# 05-STM32.net
KiCad netlist of a schematic drawn in Altium Designer
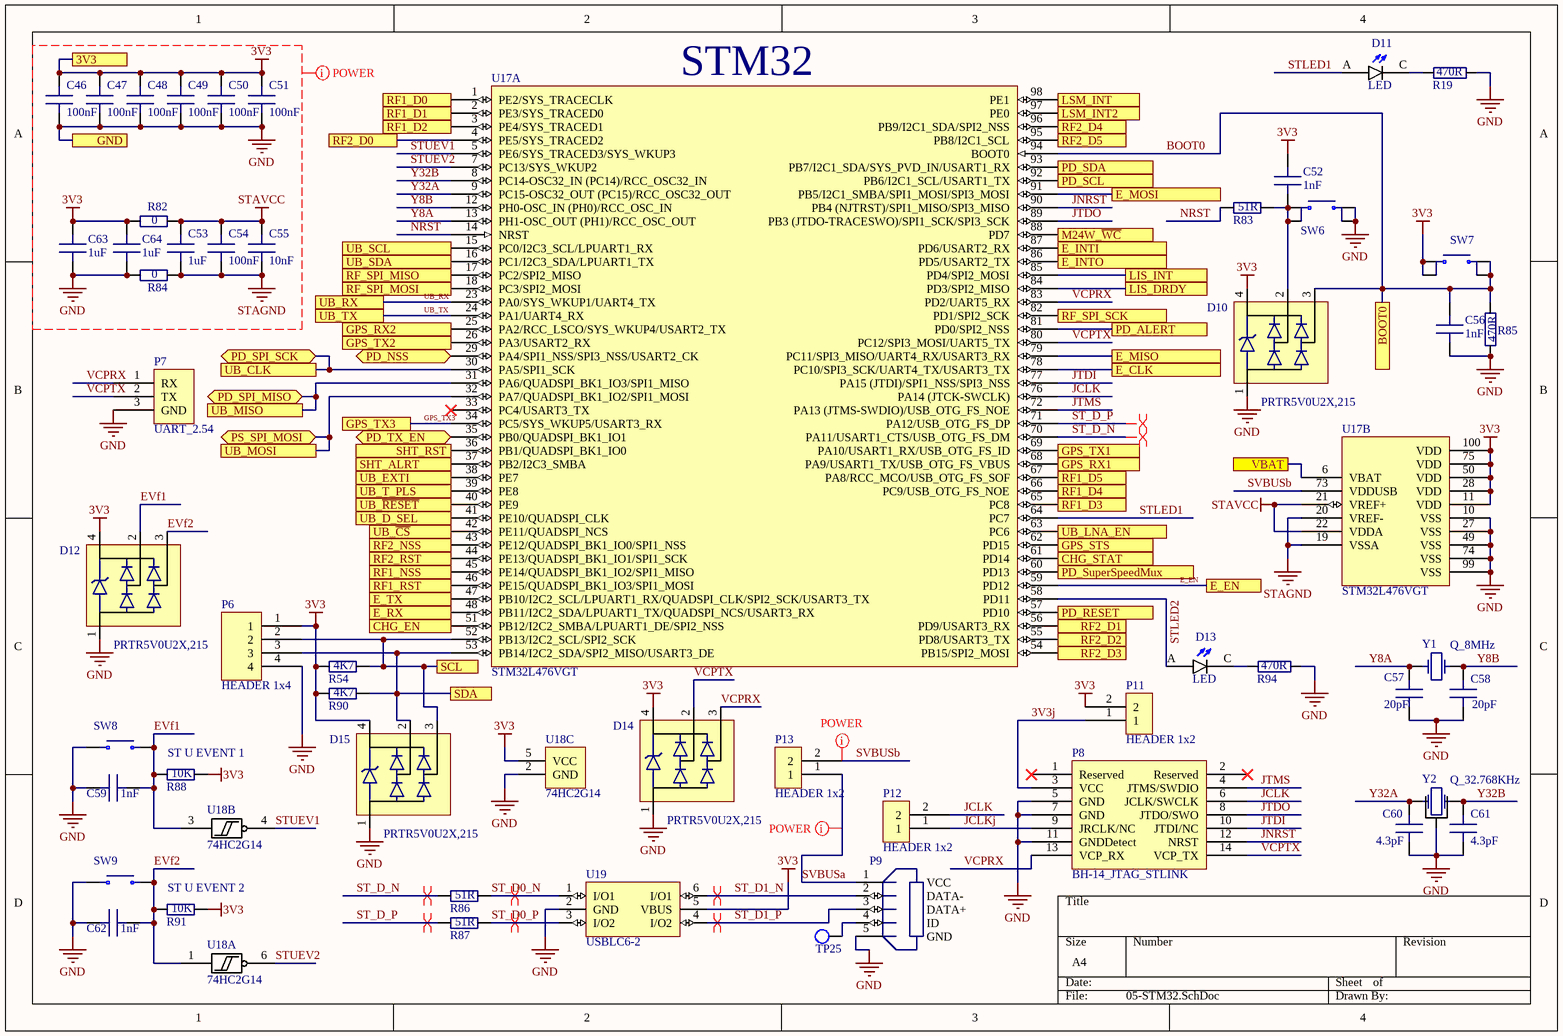
[diagram p0: 05-STM32.SchDoc]

(export (version "E")
  (design (tool "Eeschema 10.0.6"))
  (components
    (comp (ref "C46")
      (value "100nF")
      (footprint "C0603")
      (description "Ceramic capacitor")
      (fields (field (name "VOLTAGE") "16V"))
      (libsource (lib "A.Shelestov_Capacitors") (part "C0603_100nF_16V"))
    )
    (comp (ref "C47")
      (value "100nF")
      (footprint "C0603_NOSILK")
      (description "Ceramic capacitor")
      (fields (field (name "VOLTAGE") "16V"))
      (libsource (lib "A.Shelestov_Capacitors") (part "C0603_100nF_16V"))
    )
    (comp (ref "C48")
      (value "100nF")
      (footprint "C0603")
      (description "Ceramic capacitor")
      (fields (field (name "VOLTAGE") "16V"))
      (libsource (lib "A.Shelestov_Capacitors") (part "C0603_100nF_16V"))
    )
    (comp (ref "C49")
      (value "100nF")
      (footprint "C0603")
      (description "Ceramic capacitor")
      (fields (field (name "VOLTAGE") "16V"))
      (libsource (lib "A.Shelestov_Capacitors") (part "C0603_100nF_16V"))
    )
    (comp (ref "C50")
      (value "100nF")
      (footprint "C0603")
      (description "Ceramic capacitor")
      (fields (field (name "VOLTAGE") "16V"))
      (libsource (lib "A.Shelestov_Capacitors") (part "C0603_100nF_16V"))
    )
    (comp (ref "C51")
      (value "100nF")
      (footprint "C0603")
      (description "Ceramic capacitor")
      (fields (field (name "VOLTAGE") "16V"))
      (libsource (lib "A.Shelestov_Capacitors") (part "C0603_100nF_16V"))
    )
    (comp (ref "C52")
      (value "1nF")
      (footprint "C0603")
      (description "Ceramic capacitor")
      (fields (field (name "VOLTAGE") "25V"))
      (libsource (lib "A.Shelestov_Capacitors") (part "C0603_1nF_25V"))
    )
    (comp (ref "C53")
      (value "1uF")
      (footprint "C0805")
      (description "Ceramic capacitor")
      (fields (field (name "VOLTAGE") "25V"))
      (libsource (lib "A.Shelestov_Capacitors") (part "C0805_1uF_25V"))
    )
    (comp (ref "C54")
      (value "100nF")
      (footprint "C0603")
      (description "Ceramic capacitor")
      (fields (field (name "VOLTAGE") "16V"))
      (libsource (lib "A.Shelestov_Capacitors") (part "C0603_100nF_16V"))
    )
    (comp (ref "C55")
      (value "10nF")
      (footprint "C0603")
      (description "Ceramic capacitor")
      (fields (field (name "VOLTAGE") "16V"))
      (libsource (lib "A.Shelestov_Capacitors") (part "C0603_10nF_16V"))
    )
    (comp (ref "C56")
      (value "1nF")
      (footprint "C0603")
      (description "Ceramic capacitor")
      (fields (field (name "VOLTAGE") "25V"))
      (libsource (lib "A.Shelestov_Capacitors") (part "C0603_1nF_25V"))
    )
    (comp (ref "C57")
      (value "20pF")
      (footprint "C0603")
      (description "Ceramic capacitor")
      (fields (field (name "VOLTAGE") "25V"))
      (libsource (lib "A.Shelestov_Capacitors") (part "C0603_20pF_50V"))
    )
    (comp (ref "C58")
      (value "20pF")
      (footprint "C0603")
      (description "Ceramic capacitor")
      (fields (field (name "VOLTAGE") "25V"))
      (libsource (lib "A.Shelestov_Capacitors") (part "C0603_20pF_50V"))
    )
    (comp (ref "C59")
      (value "1nF")
      (footprint "C0603")
      (description "Ceramic capacitor")
      (fields (field (name "VOLTAGE") "25V"))
      (libsource (lib "A.Shelestov_Capacitors") (part "C0603_1nF_25V"))
    )
    (comp (ref "C60")
      (value "4.3pF")
      (footprint "C0603")
      (description "Ceramic capacitor")
      (fields (field (name "VOLTAGE") "25V"))
      (libsource (lib "A.Shelestov_Capacitors") (part "C0603_4.3pF_50V"))
    )
    (comp (ref "C61")
      (value "4.3pF")
      (footprint "C0603")
      (description "Ceramic capacitor")
      (fields (field (name "VOLTAGE") "25V"))
      (libsource (lib "A.Shelestov_Capacitors") (part "C0603_4.3pF_50V"))
    )
    (comp (ref "C62")
      (value "1nF")
      (footprint "C0603")
      (description "Ceramic capacitor")
      (fields (field (name "VOLTAGE") "25V"))
      (libsource (lib "A.Shelestov_Capacitors") (part "C0603_1nF_25V"))
    )
    (comp (ref "C63")
      (value "1uF")
      (footprint "C0805")
      (description "Ceramic capacitor")
      (fields (field (name "VOLTAGE") "25V"))
      (libsource (lib "A.Shelestov_Capacitors") (part "C0805_1uF_25V"))
    )
    (comp (ref "C64")
      (value "1uF")
      (footprint "C0805")
      (description "Ceramic capacitor")
      (fields (field (name "VOLTAGE") "25V"))
      (libsource (lib "A.Shelestov_Capacitors") (part "C0805_1uF_25V"))
    )
    (comp (ref "D10")
      (value "PRTR5V0U2X,215")
      (footprint "SOT143B")
      (description "PRTR5V0U2X - Ultra low capacitance double rail-to-rail ESD protection diode")
      (fields (field (name "MF") "Nexperia USA"))
      (libsource (lib "ComponentsLib") (part "PRTR5V0U2X,215"))
    )
    (comp (ref "D11")
      (value "LED")
      (footprint "LED_0604")
      (description "Led General")
      (fields (field (name "MF") "Dialight") (field (name "MP") "598-8140-107F"))
      (libsource (lib "ComponentsLib") (part "LED"))
    )
    (comp (ref "D12")
      (value "PRTR5V0U2X,215")
      (footprint "SOT143B")
      (description "PRTR5V0U2X - Ultra low capacitance double rail-to-rail ESD protection diode")
      (fields (field (name "MF") "Nexperia USA"))
      (libsource (lib "ComponentsLib") (part "PRTR5V0U2X,215"))
    )
    (comp (ref "D13")
      (value "LED")
      (footprint "LED_0604")
      (description "Led General")
      (fields (field (name "MF") "Dialight") (field (name "MP") "598-8140-107F"))
      (libsource (lib "ComponentsLib") (part "LED"))
    )
    (comp (ref "D14")
      (value "PRTR5V0U2X,215")
      (footprint "SOT143B")
      (description "PRTR5V0U2X - Ultra low capacitance double rail-to-rail ESD protection diode")
      (fields (field (name "MF") "Nexperia USA"))
      (libsource (lib "ComponentsLib") (part "PRTR5V0U2X,215"))
    )
    (comp (ref "D15")
      (value "PRTR5V0U2X,215")
      (footprint "SOT143B")
      (description "PRTR5V0U2X - Ultra low capacitance double rail-to-rail ESD protection diode")
      (fields (field (name "MF") "Nexperia USA"))
      (libsource (lib "ComponentsLib") (part "PRTR5V0U2X,215"))
    )
    (comp (ref "P6")
      (value "HEADER 1x4")
      (footprint "HEADER 1x4 2.54")
      (libsource (lib "ComponentsLib") (part "HEADER 1x4"))
    )
    (comp (ref "P7")
      (value "UART_2.54")
      (footprint "UART_2.54")
      (libsource (lib "ComponentsLib") (part "UART_2.54"))
    )
    (comp (ref "P8")
      (value "BH-14_JTAG_STLINK")
      (footprint "BH-14-1.27")
      (description "1,27 mm 2x7 Header")
      (libsource (lib "ComponentsLib") (part "BH-14_JTAG_STLINK"))
    )
    (comp (ref "P9")
      (value "440247-2")
      (footprint "CON-UUSB-F-2")
      (description "Mini/Micro USB B Type RCPT")
      (fields (field (name "MF") "TE Connectivity"))
      (libsource (lib "ComponentsLib") (part "CON-USB-Micro/Mini"))
    )
    (comp (ref "P11")
      (value "HEADER 1x2")
      (footprint "HEADER 1x2 2.54")
      (libsource (lib "") (part "HEADER 1x2_1"))
    )
    (comp (ref "P12")
      (value "HEADER 1x2")
      (footprint "HEADER 1x2 2.54")
      (libsource (lib "ComponentsLib") (part "HEADER 1x2"))
    )
    (comp (ref "P13")
      (value "HEADER 1x2")
      (footprint "HEADER 1x2 2.54")
      (libsource (lib "ComponentsLib") (part "HEADER 1x2"))
    )
    (comp (ref "R19")
      (value "~")
      (footprint "R0603")
      (description "Resistor General")
      (fields (field (name "TOLERANCE") "5%") (field (name "RESISTANCE") "470R"))
      (libsource (lib "A.Shelestov_Resistors") (part "R0603_470R"))
    )
    (comp (ref "R54")
      (value "~")
      (footprint "R0603")
      (description "Resistor General")
      (fields (field (name "TOLERANCE") "5%") (field (name "RESISTANCE") "4K7"))
      (libsource (lib "A.Shelestov_Resistors") (part "R0603_4K7"))
    )
    (comp (ref "R82")
      (value "~")
      (footprint "R0603")
      (description "Resistor General")
      (fields (field (name "RESISTANCE") "0"))
      (libsource (lib "A.Shelestov_Resistors") (part "R0603_0R"))
    )
    (comp (ref "R83")
      (value "~")
      (footprint "R0402")
      (description "Resistor General")
      (fields (field (name "RESISTANCE") "51R"))
      (libsource (lib "A.Shelestov_Resistors") (part "R0402_51R"))
    )
    (comp (ref "R84")
      (value "~")
      (footprint "R0603")
      (description "Resistor General")
      (fields (field (name "RESISTANCE") "0"))
      (libsource (lib "A.Shelestov_Resistors") (part "R0603_0R"))
    )
    (comp (ref "R85")
      (value "~")
      (footprint "R0603")
      (description "Resistor General")
      (fields (field (name "TOLERANCE") "5%") (field (name "RESISTANCE") "470R"))
      (libsource (lib "A.Shelestov_Resistors") (part "R0603_470R"))
    )
    (comp (ref "R86")
      (value "~")
      (footprint "R0402")
      (description "Resistor General")
      (fields (field (name "RESISTANCE") "51R"))
      (libsource (lib "A.Shelestov_Resistors") (part "R0402_51R"))
    )
    (comp (ref "R87")
      (value "~")
      (footprint "R0402")
      (description "Resistor General")
      (fields (field (name "RESISTANCE") "51R"))
      (libsource (lib "A.Shelestov_Resistors") (part "R0402_51R"))
    )
    (comp (ref "R88")
      (value "~")
      (footprint "R0603")
      (description "Resistor General")
      (fields (field (name "TOLERANCE") "5%") (field (name "RESISTANCE") "10K"))
      (libsource (lib "A.Shelestov_Resistors") (part "R0603_10K"))
    )
    (comp (ref "R90")
      (value "~")
      (footprint "R0603")
      (description "Resistor General")
      (fields (field (name "TOLERANCE") "5%") (field (name "RESISTANCE") "4K7"))
      (libsource (lib "A.Shelestov_Resistors") (part "R0603_4K7"))
    )
    (comp (ref "R91")
      (value "~")
      (footprint "R0603")
      (description "Resistor General")
      (fields (field (name "TOLERANCE") "5%") (field (name "RESISTANCE") "10K"))
      (libsource (lib "A.Shelestov_Resistors") (part "R0603_10K"))
    )
    (comp (ref "R94")
      (value "~")
      (footprint "R0603")
      (description "Resistor General")
      (fields (field (name "TOLERANCE") "5%") (field (name "RESISTANCE") "470R"))
      (libsource (lib "A.Shelestov_Resistors") (part "R0603_470R"))
    )
    (comp (ref "SW6")
      (value "SWITCH_GEN_4P")
      (footprint "SW_4x4x1.5")
      (description "SWITCH DIP 4.3 mm")
      (libsource (lib "ComponentsLib") (part "SWITCH_GEN_4P"))
    )
    (comp (ref "SW7")
      (value "SWITCH_GEN_4P")
      (footprint "SW_4x4x1.5")
      (description "SWITCH DIP 4.3 mm")
      (libsource (lib "ComponentsLib") (part "SWITCH_GEN_4P"))
    )
    (comp (ref "SW8")
      (value "SWITCH_GEN_2P")
      (footprint "SW_TACTM-35N-F")
      (description "SWITCH DIP 4.3 mm")
      (libsource (lib "ComponentsLib") (part "SWITCH_GEN_2P"))
    )
    (comp (ref "SW9")
      (value "SWITCH_GEN_2P")
      (footprint "SW_TACTM-35N-F")
      (description "SWITCH DIP 4.3 mm")
      (libsource (lib "ComponentsLib") (part "SWITCH_GEN_2P"))
    )
    (comp (ref "TP25")
      (value "TEST_POINT")
      (footprint "TP_1mm")
      (libsource (lib "ComponentsLib") (part "TEST_POINT"))
    )
    (comp (ref "U17")
      (value "STM32L476VGT")
      (footprint "LQFP100_0.5")
      (description "Ultra-low-power Cortex-M4 32-bit MCU+FPU, 100DMIPS, up to 1MB Flash, 128 KB SRAM, USB OTG FS, LCD")
      (libsource (lib "ComponentsLib") (part "STM32L476VGT"))
    )
    (comp (ref "U18")
      (value "74HC2G14")
      (footprint "SOT363/SOT65P210X110-6N")
      (description "Dual inverting Schmitt trigger")
      (libsource (lib "ComponentsLib") (part "74HC2G14"))
    )
    (comp (ref "U19")
      (value "USBLC6-2")
      (footprint "SOT-666")
      (description "Very low capacitance ESD protection")
      (libsource (lib "ComponentsLib") (part "USBLC6-2"))
    )
    (comp (ref "Y1")
      (value "Q_8MHz")
      (footprint "QSMD12.3x4.5x4.2")
      (description "Quartz resonator 8MHz")
      (libsource (lib "ComponentsLib") (part "Q_8MHz"))
    )
    (comp (ref "Y2")
      (value "Q_32.768KHz")
      (footprint "HC_3.0x8.0")
      (description "Quartz resonator 32.768KHz")
      (libsource (lib "ComponentsLib") (part "Q_32.768KHz"))
    )
  )
  (nets
    (net (code "1") (name "/3V3j") (class "Default")
      (node (ref "P11") (pin "1") (pinfunction "1_1") (pintype "passive"))
      (node (ref "P8") (pin "3") (pinfunction "VCC_3") (pintype "passive"))
    )
    (net (code "2") (name "/BOOT0") (class "Default")
      (node (ref "C56") (pin "1") (pinfunction "1_1") (pintype "passive"))
      (node (ref "D10") (pin "3") (pinfunction "P$3_3") (pintype "passive"))
      (node (ref "R85") (pin "2") (pinfunction "2_2") (pintype "passive"))
      (node (ref "SW7") (pin "1") (pinfunction "1_1") (pintype "passive"))
      (node (ref "SW7") (pin "3") (pinfunction "3_3") (pintype "passive"))
      (node (ref "U17") (pin "94") (pinfunction "BOOT0_94") (pintype "input"))
    )
    (net (code "3") (name "/CHG_EN") (class "Default")
      (node (ref "U17") (pin "51") (pinfunction "PB12/I2C2_SMBA/LPUART1_DE/SPI2_NSS_51") (pintype "bidirectional"))
    )
    (net (code "4") (name "/CHG_STAT") (class "Default")
      (node (ref "U17") (pin "61") (pinfunction "PD14_61") (pintype "bidirectional"))
    )
    (net (code "5") (name "/EVf1") (class "Default")
      (node (ref "C59") (pin "1") (pinfunction "1_1") (pintype "passive"))
      (node (ref "D12") (pin "2") (pinfunction "P$2_2") (pintype "passive"))
      (node (ref "R88") (pin "1") (pinfunction "1_1") (pintype "passive"))
      (node (ref "SW8") (pin "2") (pinfunction "2_2") (pintype "passive"))
      (node (ref "U18") (pin "3") (pinfunction "2A_3") (pintype "passive"))
    )
    (net (code "6") (name "/EVf2") (class "Default")
      (node (ref "C62") (pin "1") (pinfunction "1_1") (pintype "passive"))
      (node (ref "D12") (pin "3") (pinfunction "P$3_3") (pintype "passive"))
      (node (ref "R91") (pin "1") (pinfunction "1_1") (pintype "passive"))
      (node (ref "SW9") (pin "2") (pinfunction "2_2") (pintype "passive"))
      (node (ref "U18") (pin "1") (pinfunction "1A_1") (pintype "passive"))
    )
    (net (code "7") (name "/E_CLK") (class "Default")
      (node (ref "U17") (pin "78") (pinfunction "PC10/SPI3_SCK/UART4_TX/USART3_TX_78") (pintype "bidirectional"))
    )
    (net (code "8") (name "/E_EN") (class "Default")
      (node (ref "U17") (pin "59") (pinfunction "PD12_59") (pintype "bidirectional"))
    )
    (net (code "9") (name "/E_INTI") (class "Default")
      (node (ref "U17") (pin "87") (pinfunction "PD6/USART2_RX_87") (pintype "bidirectional"))
    )
    (net (code "10") (name "/E_INTO") (class "Default")
      (node (ref "U17") (pin "86") (pinfunction "PD5/USART2_TX_86") (pintype "bidirectional"))
    )
    (net (code "11") (name "/E_MISO") (class "Default")
      (node (ref "U17") (pin "79") (pinfunction "PC11/SPI3_MISO/UART4_RX/USART3_RX_79") (pintype "bidirectional"))
    )
    (net (code "12") (name "/E_MOSI") (class "Default")
      (node (ref "U17") (pin "91") (pinfunction "PB5/I2C1_SMBA/SPI1_MOSI/SPI3_MOSI_91") (pintype "bidirectional"))
    )
    (net (code "13") (name "/E_RX") (class "Default")
      (node (ref "U17") (pin "48") (pinfunction "PB11/I2C2_SDA/LPUART1_TX/QUADSPI_NCS/USART3_RX_48") (pintype "bidirectional"))
    )
    (net (code "14") (name "/E_TX") (class "Default")
      (node (ref "U17") (pin "47") (pinfunction "PB10/I2C2_SCL/LPUART1_RX/QUADSPI_CLK/SPI2_SCK/USART3_TX_47") (pintype "bidirectional"))
    )
    (net (code "15") (name "/GPS_RX1") (class "Default")
      (node (ref "U17") (pin "68") (pinfunction "PA9/USART1_TX/USB_OTG_FS_VBUS_68") (pintype "bidirectional"))
    )
    (net (code "16") (name "/GPS_RX2") (class "Default")
      (node (ref "U17") (pin "25") (pinfunction "PA2/RCC_LSCO/SYS_WKUP4/USART2_TX_25") (pintype "bidirectional"))
    )
    (net (code "17") (name "/GPS_STS") (class "Default")
      (node (ref "U17") (pin "62") (pinfunction "PD15_62") (pintype "bidirectional"))
    )
    (net (code "18") (name "/GPS_TX1") (class "Default")
      (node (ref "U17") (pin "69") (pinfunction "PA10/USART1_RX/USB_OTG_FS_ID_69") (pintype "bidirectional"))
    )
    (net (code "19") (name "/GPS_TX2") (class "Default")
      (node (ref "U17") (pin "26") (pinfunction "PA3/USART2_RX_26") (pintype "bidirectional"))
    )
    (net (code "20") (name "/GPS_TX3") (class "Default")
      (node (ref "U17") (pin "34") (pinfunction "PC5/SYS_WKUP5/USART3_RX_34") (pintype "bidirectional"))
    )
    (net (code "21") (name "/JCLK") (class "Default")
      (node (ref "P12") (pin "2") (pinfunction "2_2") (pintype "passive"))
      (node (ref "P8") (pin "6") (pinfunction "JCLK/SWCLK_6") (pintype "passive"))
      (node (ref "U17") (pin "76") (pinfunction "PA14_(JTCK-SWCLK)_76") (pintype "bidirectional"))
    )
    (net (code "22") (name "/JCLKj") (class "Default")
      (node (ref "P12") (pin "1") (pinfunction "1_1") (pintype "passive"))
      (node (ref "P8") (pin "9") (pinfunction "JRCLK/NC_9") (pintype "passive"))
    )
    (net (code "23") (name "/JNRST") (class "Default")
      (node (ref "P8") (pin "12") (pinfunction "NRST_12") (pintype "passive"))
      (node (ref "U17") (pin "90") (pinfunction "PB4_(NJTRST)/SPI1_MISO/SPI3_MISO_90") (pintype "bidirectional"))
    )
    (net (code "24") (name "/JTDI") (class "Default")
      (node (ref "P8") (pin "10") (pinfunction "JTDI/NC_10") (pintype "passive"))
      (node (ref "U17") (pin "77") (pinfunction "PA15_(JTDI)/SPI1_NSS/SPI3_NSS_77") (pintype "bidirectional"))
    )
    (net (code "25") (name "/JTDO") (class "Default")
      (node (ref "P8") (pin "8") (pinfunction "JTDO/SWO_8") (pintype "passive"))
      (node (ref "U17") (pin "89") (pinfunction "PB3_(JTDO-TRACESWO)/SPI1_SCK/SPI3_SCK_89") (pintype "bidirectional"))
    )
    (net (code "26") (name "/JTMS") (class "Default")
      (node (ref "P8") (pin "4") (pinfunction "JTMS/SWDIO_4") (pintype "passive"))
      (node (ref "U17") (pin "72") (pinfunction "PA13_(JTMS-SWDIO)/USB_OTG_FS_NOE_72") (pintype "bidirectional"))
    )
    (net (code "27") (name "/LIS_DRDY") (class "Default")
      (node (ref "U17") (pin "84") (pinfunction "PD3/SPI2_MISO_84") (pintype "bidirectional"))
    )
    (net (code "28") (name "/LIS_INT") (class "Default")
      (node (ref "U17") (pin "85") (pinfunction "PD4/SPI2_MOSI_85") (pintype "bidirectional"))
    )
    (net (code "29") (name "/LSM_INT") (class "Default")
      (node (ref "U17") (pin "98") (pinfunction "PE1_98") (pintype "bidirectional"))
    )
    (net (code "30") (name "/LSM_INT2") (class "Default")
      (node (ref "U17") (pin "97") (pinfunction "PE0_97") (pintype "bidirectional"))
    )
    (net (code "31") (name "/M24W_~{WC}") (class "Default")
      (node (ref "U17") (pin "88") (pinfunction "PD7_88") (pintype "bidirectional"))
    )
    (net (code "32") (name "/NRST") (class "Default")
      (node (ref "R83") (pin "1") (pinfunction "1_1") (pintype "passive"))
      (node (ref "U17") (pin "14") (pinfunction "NRST_14") (pintype "input"))
    )
    (net (code "33") (name "/PD_ALERT") (class "Default")
      (node (ref "U17") (pin "81") (pinfunction "PD0/SPI2_NSS_81") (pintype "bidirectional"))
    )
    (net (code "34") (name "/PD_NSS") (class "Default")
      (node (ref "U17") (pin "29") (pinfunction "PA4/SPI1_NSS/SPI3_NSS/USART2_CK_29") (pintype "bidirectional"))
    )
    (net (code "35") (name "/PD_RESET") (class "Default")
      (node (ref "U17") (pin "57") (pinfunction "PD10_57") (pintype "bidirectional"))
    )
    (net (code "36") (name "/PD_SCL") (class "Default")
      (node (ref "U17") (pin "92") (pinfunction "PB6/I2C1_SCL/USART1_TX_92") (pintype "bidirectional"))
    )
    (net (code "37") (name "/PD_SDA") (class "Default")
      (node (ref "U17") (pin "93") (pinfunction "PB7/I2C1_SDA/SYS_PVD_IN/USART1_RX_93") (pintype "bidirectional"))
    )
    (net (code "38") (name "/PD_SPI_MISO") (class "Default")
      (node (ref "U17") (pin "31") (pinfunction "PA6/QUADSPI_BK1_IO3/SPI1_MISO_31") (pintype "bidirectional"))
    )
    (net (code "39") (name "/PD_SPI_SCK") (class "Default")
      (node (ref "U17") (pin "30") (pinfunction "PA5/SPI1_SCK_30") (pintype "bidirectional"))
    )
    (net (code "40") (name "/PD_SuperSpeedMux") (class "Default")
      (node (ref "U17") (pin "60") (pinfunction "PD13_60") (pintype "bidirectional"))
    )
    (net (code "41") (name "/PD_TX_EN") (class "Default")
      (node (ref "U17") (pin "35") (pinfunction "PB0/QUADSPI_BK1_IO1_35") (pintype "bidirectional"))
    )
    (net (code "42") (name "/PS_SPI_MOSI") (class "Default")
      (node (ref "U17") (pin "32") (pinfunction "PA7/QUADSPI_BK1_IO2/SPI1_MOSI_32") (pintype "bidirectional"))
    )
    (net (code "43") (name "/RF1_D0") (class "Default")
      (node (ref "U17") (pin "1") (pinfunction "PE2/SYS_TRACECLK_1") (pintype "bidirectional"))
    )
    (net (code "44") (name "/RF1_D1") (class "Default")
      (node (ref "U17") (pin "2") (pinfunction "PE3/SYS_TRACED0_2") (pintype "bidirectional"))
    )
    (net (code "45") (name "/RF1_D2") (class "Default")
      (node (ref "U17") (pin "3") (pinfunction "PE4/SYS_TRACED1_3") (pintype "bidirectional"))
    )
    (net (code "46") (name "/RF1_D3") (class "Default")
      (node (ref "U17") (pin "65") (pinfunction "PC8_65") (pintype "bidirectional"))
    )
    (net (code "47") (name "/RF1_D4") (class "Default")
      (node (ref "U17") (pin "66") (pinfunction "PC9/USB_OTG_FS_NOE_66") (pintype "bidirectional"))
    )
    (net (code "48") (name "/RF1_D5") (class "Default")
      (node (ref "U17") (pin "67") (pinfunction "PA8/RCC_MCO/USB_OTG_FS_SOF_67") (pintype "bidirectional"))
    )
    (net (code "49") (name "/RF1_NSS") (class "Default")
      (node (ref "U17") (pin "45") (pinfunction "PE14/QUADSPI_BK1_IO2/SPI1_MISO_45") (pintype "bidirectional"))
    )
    (net (code "50") (name "/RF1_RST") (class "Default")
      (node (ref "U17") (pin "46") (pinfunction "PE15/QUADSPI_BK1_IO3/SPI1_MOSI_46") (pintype "bidirectional"))
    )
    (net (code "51") (name "/RF2_D0") (class "Default")
      (node (ref "U17") (pin "4") (pinfunction "PE5/SYS_TRACED2_4") (pintype "bidirectional"))
    )
    (net (code "52") (name "/RF2_D1") (class "Default")
      (node (ref "U17") (pin "56") (pinfunction "PD9/USART3_RX_56") (pintype "bidirectional"))
    )
    (net (code "53") (name "/RF2_D2") (class "Default")
      (node (ref "U17") (pin "55") (pinfunction "PD8/USART3_TX_55") (pintype "bidirectional"))
    )
    (net (code "54") (name "/RF2_D3") (class "Default")
      (node (ref "U17") (pin "54") (pinfunction "PB15/SPI2_MOSI_54") (pintype "bidirectional"))
    )
    (net (code "55") (name "/RF2_D4") (class "Default")
      (node (ref "U17") (pin "96") (pinfunction "PB9/I2C1_SDA/SPI2_NSS_96") (pintype "bidirectional"))
    )
    (net (code "56") (name "/RF2_D5") (class "Default")
      (node (ref "U17") (pin "95") (pinfunction "PB8/I2C1_SCL_95") (pintype "bidirectional"))
    )
    (net (code "57") (name "/RF2_NSS") (class "Default")
      (node (ref "U17") (pin "43") (pinfunction "PE12/QUADSPI_BK1_IO0/SPI1_NSS_43") (pintype "bidirectional"))
    )
    (net (code "58") (name "/RF2_RST") (class "Default")
      (node (ref "U17") (pin "44") (pinfunction "PE13/QUADSPI_BK1_IO1/SPI1_SCK_44") (pintype "bidirectional"))
    )
    (net (code "59") (name "/RF_SPI_MISO") (class "Default")
      (node (ref "U17") (pin "17") (pinfunction "PC2/SPI2_MISO_17") (pintype "bidirectional"))
    )
    (net (code "60") (name "/RF_SPI_MOSI") (class "Default")
      (node (ref "U17") (pin "18") (pinfunction "PC3/SPI2_MOSI_18") (pintype "bidirectional"))
    )
    (net (code "61") (name "/RF_SPI_SCK") (class "Default")
      (node (ref "U17") (pin "82") (pinfunction "PD1/SPI2_SCK_82") (pintype "bidirectional"))
    )
    (net (code "62") (name "/SCL") (class "Default")
      (node (ref "D15") (pin "3") (pinfunction "P$3_3") (pintype "passive"))
      (node (ref "P6") (pin "2") (pinfunction "2_2") (pintype "passive"))
      (node (ref "R54") (pin "2") (pinfunction "2_2") (pintype "passive"))
      (node (ref "U17") (pin "52") (pinfunction "PB13/I2C2_SCL/SPI2_SCK_52") (pintype "bidirectional"))
    )
    (net (code "63") (name "/SDA") (class "Default")
      (node (ref "D15") (pin "2") (pinfunction "P$2_2") (pintype "passive"))
      (node (ref "P6") (pin "3") (pinfunction "3_3") (pintype "passive"))
      (node (ref "R90") (pin "2") (pinfunction "2_2") (pintype "passive"))
      (node (ref "U17") (pin "53") (pinfunction "PB14/I2C2_SDA/SPI2_MISO/USART3_DE_53") (pintype "bidirectional"))
    )
    (net (code "64") (name "/SHT_ALRT") (class "Default")
      (node (ref "U17") (pin "37") (pinfunction "PB2/I2C3_SMBA_37") (pintype "bidirectional"))
    )
    (net (code "65") (name "/SHT_RST") (class "Default")
      (node (ref "U17") (pin "36") (pinfunction "PB1/QUADSPI_BK1_IO0_36") (pintype "bidirectional"))
    )
    (net (code "66") (name "/STLED1") (class "Default")
      (node (ref "D11") (pin "A") (pinfunction "A_A") (pintype "passive"))
      (node (ref "U17") (pin "64") (pinfunction "PC7_64") (pintype "bidirectional"))
    )
    (net (code "67") (name "/STLED2") (class "Default")
      (node (ref "D13") (pin "A") (pinfunction "A_A") (pintype "passive"))
      (node (ref "U17") (pin "58") (pinfunction "PD11_58") (pintype "bidirectional"))
    )
    (net (code "68") (name "/STUEV1") (class "Default")
      (node (ref "U17") (pin "5") (pinfunction "PE6/SYS_TRACED3/SYS_WKUP3_5") (pintype "bidirectional"))
      (node (ref "U18") (pin "4") (pinfunction "2Y_4") (pintype "passive"))
    )
    (net (code "69") (name "/STUEV2") (class "Default")
      (node (ref "U17") (pin "7") (pinfunction "PC13/SYS_WKUP2_7") (pintype "bidirectional"))
      (node (ref "U18") (pin "6") (pinfunction "1Y_6") (pintype "passive"))
    )
    (net (code "70") (name "/ST_D0_N") (class "Default")
      (node (ref "R86") (pin "2") (pinfunction "2_2") (pintype "passive"))
      (node (ref "U19") (pin "1") (pinfunction "I/O1_1") (pintype "bidirectional"))
    )
    (net (code "71") (name "/ST_D0_P") (class "Default")
      (node (ref "R87") (pin "2") (pinfunction "2_2") (pintype "passive"))
      (node (ref "U19") (pin "3") (pinfunction "I/O2_3") (pintype "bidirectional"))
    )
    (net (code "72") (name "/ST_D1_N") (class "Default")
      (node (ref "P9") (pin "2") (pinfunction "DATA-_2") (pintype "bidirectional"))
      (node (ref "U19") (pin "6") (pinfunction "I/O1_6") (pintype "bidirectional"))
    )
    (net (code "73") (name "/ST_D1_P") (class "Default")
      (node (ref "P9") (pin "3") (pinfunction "DATA+_3") (pintype "bidirectional"))
      (node (ref "U19") (pin "4") (pinfunction "I/O2_4") (pintype "bidirectional"))
    )
    (net (code "74") (name "/ST_D_N") (class "Default")
      (node (ref "R86") (pin "1") (pinfunction "1_1") (pintype "passive"))
      (node (ref "U17") (pin "70") (pinfunction "PA11/USART1_CTS/USB_OTG_FS_DM_70") (pintype "bidirectional"))
    )
    (net (code "75") (name "/ST_D_P") (class "Default")
      (node (ref "R87") (pin "1") (pinfunction "1_1") (pintype "passive"))
      (node (ref "U17") (pin "71") (pinfunction "PA12/USB_OTG_FS_DP_71") (pintype "bidirectional"))
    )
    (net (code "76") (name "/SVBUSa") (class "Default")
      (node (ref "P13") (pin "1") (pinfunction "1_1") (pintype "passive"))
      (node (ref "P9") (pin "1") (pinfunction "VCC_1") (pintype "power_in"))
    )
    (net (code "77") (name "/SVBUSb") (class "Default")
      (node (ref "P13") (pin "2") (pinfunction "2_2") (pintype "passive"))
      (node (ref "U17") (pin "73") (pinfunction "VDDUSB_73") (pintype "power_in"))
    )
    (net (code "78") (name "/UB_D_SEL") (class "Default")
      (node (ref "U17") (pin "41") (pinfunction "PE10/QUADSPI_CLK_41") (pintype "bidirectional"))
    )
    (net (code "79") (name "/UB_EXTI") (class "Default")
      (node (ref "U17") (pin "38") (pinfunction "PE7_38") (pintype "bidirectional"))
    )
    (net (code "80") (name "/UB_LNA_EN") (class "Default")
      (node (ref "U17") (pin "63") (pinfunction "PC6_63") (pintype "bidirectional"))
    )
    (net (code "81") (name "/UB_RX") (class "Default")
      (node (ref "U17") (pin "23") (pinfunction "PA0/SYS_WKUP1/UART4_TX_23") (pintype "bidirectional"))
    )
    (net (code "82") (name "/UB_SCL") (class "Default")
      (node (ref "U17") (pin "15") (pinfunction "PC0/I2C3_SCL/LPUART1_RX_15") (pintype "bidirectional"))
    )
    (net (code "83") (name "/UB_SDA") (class "Default")
      (node (ref "U17") (pin "16") (pinfunction "PC1/I2C3_SDA/LPUART1_TX_16") (pintype "bidirectional"))
    )
    (net (code "84") (name "/UB_TX") (class "Default")
      (node (ref "U17") (pin "24") (pinfunction "PA1/UART4_RX_24") (pintype "bidirectional"))
    )
    (net (code "85") (name "/UB_T_PLS") (class "Default")
      (node (ref "U17") (pin "39") (pinfunction "PE8_39") (pintype "bidirectional"))
    )
    (net (code "86") (name "/UB_~{CS}") (class "Default")
      (node (ref "U17") (pin "42") (pinfunction "PE11/QUADSPI_NCS_42") (pintype "bidirectional"))
    )
    (net (code "87") (name "/UB_~{RESET}") (class "Default")
      (node (ref "U17") (pin "40") (pinfunction "PE9_40") (pintype "bidirectional"))
    )
    (net (code "88") (name "/VBAT") (class "Default")
      (node (ref "U17") (pin "6") (pinfunction "VBAT_6") (pintype "power_in"))
    )
    (net (code "89") (name "/VCPRX") (class "Default")
      (node (ref "D14") (pin "3") (pinfunction "P$3_3") (pintype "passive"))
      (node (ref "P7") (pin "1") (pinfunction "RX_1") (pintype "passive"))
      (node (ref "P8") (pin "13") (pinfunction "VCP_RX_13") (pintype "passive"))
      (node (ref "U17") (pin "83") (pinfunction "PD2/UART5_RX_83") (pintype "bidirectional"))
    )
    (net (code "90") (name "/VCPTX") (class "Default")
      (node (ref "D14") (pin "2") (pinfunction "P$2_2") (pintype "passive"))
      (node (ref "P7") (pin "2") (pinfunction "TX_2") (pintype "passive"))
      (node (ref "P8") (pin "14") (pinfunction "VCP_TX_14") (pintype "passive"))
      (node (ref "U17") (pin "80") (pinfunction "PC12/SPI3_MOSI/UART5_TX_80") (pintype "bidirectional"))
    )
    (net (code "91") (name "/Y8A") (class "Default")
      (node (ref "C57") (pin "2") (pinfunction "2_2") (pintype "passive"))
      (node (ref "U17") (pin "13") (pinfunction "PH1-OSC_OUT_(PH1)/RCC_OSC_OUT_13") (pintype "bidirectional"))
      (node (ref "Y1") (pin "1") (pinfunction "1_1") (pintype "passive"))
    )
    (net (code "92") (name "/Y8B") (class "Default")
      (node (ref "C58") (pin "2") (pinfunction "2_2") (pintype "passive"))
      (node (ref "U17") (pin "12") (pinfunction "PH0-OSC_IN_(PH0)/RCC_OSC_IN_12") (pintype "bidirectional"))
      (node (ref "Y1") (pin "2") (pinfunction "2_2") (pintype "passive"))
    )
    (net (code "93") (name "/Y32A") (class "Default")
      (node (ref "C60") (pin "2") (pinfunction "2_2") (pintype "passive"))
      (node (ref "U17") (pin "9") (pinfunction "PC15-OSC32_OUT_(PC15)/RCC_OSC32_OUT_9") (pintype "bidirectional"))
      (node (ref "Y2") (pin "1") (pinfunction "1_1") (pintype "passive"))
    )
    (net (code "94") (name "/Y32B") (class "Default")
      (node (ref "C61") (pin "2") (pinfunction "2_2") (pintype "passive"))
      (node (ref "U17") (pin "8") (pinfunction "PC14-OSC32_IN_(PC14)/RCC_OSC32_IN_8") (pintype "bidirectional"))
      (node (ref "Y2") (pin "2") (pinfunction "2_2") (pintype "passive"))
    )
    (net (code "95") (name "3V3") (class "Default")
      (node (ref "C46") (pin "2") (pinfunction "2_2") (pintype "passive"))
      (node (ref "C47") (pin "2") (pinfunction "2_2") (pintype "passive"))
      (node (ref "C48") (pin "2") (pinfunction "2_2") (pintype "passive"))
      (node (ref "C49") (pin "2") (pinfunction "2_2") (pintype "passive"))
      (node (ref "C50") (pin "2") (pinfunction "2_2") (pintype "passive"))
      (node (ref "C51") (pin "2") (pinfunction "2_2") (pintype "passive"))
      (node (ref "C52") (pin "1") (pinfunction "1_1") (pintype "passive"))
      (node (ref "C63") (pin "2") (pinfunction "2_2") (pintype "passive"))
      (node (ref "C64") (pin "2") (pinfunction "2_2") (pintype "passive"))
      (node (ref "D10") (pin "4") (pinfunction "P$4_4") (pintype "passive"))
      (node (ref "D12") (pin "4") (pinfunction "P$4_4") (pintype "passive"))
      (node (ref "D14") (pin "4") (pinfunction "P$4_4") (pintype "passive"))
      (node (ref "D15") (pin "4") (pinfunction "P$4_4") (pintype "passive"))
      (node (ref "P11") (pin "2") (pinfunction "2_2") (pintype "passive"))
      (node (ref "P6") (pin "1") (pinfunction "1_1") (pintype "passive"))
      (node (ref "R54") (pin "1") (pinfunction "1_1") (pintype "passive"))
      (node (ref "R82") (pin "1") (pinfunction "1_1") (pintype "passive"))
      (node (ref "R88") (pin "2") (pinfunction "2_2") (pintype "passive"))
      (node (ref "R90") (pin "1") (pinfunction "1_1") (pintype "passive"))
      (node (ref "R91") (pin "2") (pinfunction "2_2") (pintype "passive"))
      (node (ref "SW7") (pin "2") (pinfunction "2_2") (pintype "passive"))
      (node (ref "SW7") (pin "4") (pinfunction "4_4") (pintype "passive"))
      (node (ref "U17") (pin "100") (pinfunction "VDD_100") (pintype "power_in"))
      (node (ref "U17") (pin "11") (pinfunction "VDD_11") (pintype "power_in"))
      (node (ref "U17") (pin "28") (pinfunction "VDD_28") (pintype "power_in"))
      (node (ref "U17") (pin "50") (pinfunction "VDD_50") (pintype "power_in"))
      (node (ref "U17") (pin "75") (pinfunction "VDD_75") (pintype "power_in"))
      (node (ref "U18") (pin "5") (pinfunction "VCC_5") (pintype "passive"))
      (node (ref "U19") (pin "5") (pinfunction "VBUS_5") (pintype "power_in"))
    )
    (net (code "96") (name "GND") (class "Default")
      (node (ref "C46") (pin "1") (pinfunction "1_1") (pintype "passive"))
      (node (ref "C47") (pin "1") (pinfunction "1_1") (pintype "passive"))
      (node (ref "C48") (pin "1") (pinfunction "1_1") (pintype "passive"))
      (node (ref "C49") (pin "1") (pinfunction "1_1") (pintype "passive"))
      (node (ref "C50") (pin "1") (pinfunction "1_1") (pintype "passive"))
      (node (ref "C51") (pin "1") (pinfunction "1_1") (pintype "passive"))
      (node (ref "C56") (pin "2") (pinfunction "2_2") (pintype "passive"))
      (node (ref "C57") (pin "1") (pinfunction "1_1") (pintype "passive"))
      (node (ref "C58") (pin "1") (pinfunction "1_1") (pintype "passive"))
      (node (ref "C59") (pin "2") (pinfunction "2_2") (pintype "passive"))
      (node (ref "C60") (pin "1") (pinfunction "1_1") (pintype "passive"))
      (node (ref "C61") (pin "1") (pinfunction "1_1") (pintype "passive"))
      (node (ref "C62") (pin "2") (pinfunction "2_2") (pintype "passive"))
      (node (ref "C63") (pin "1") (pinfunction "1_1") (pintype "passive"))
      (node (ref "C64") (pin "1") (pinfunction "1_1") (pintype "passive"))
      (node (ref "D10") (pin "1") (pinfunction "P$1_1") (pintype "passive"))
      (node (ref "D12") (pin "1") (pinfunction "P$1_1") (pintype "passive"))
      (node (ref "D14") (pin "1") (pinfunction "P$1_1") (pintype "passive"))
      (node (ref "D15") (pin "1") (pinfunction "P$1_1") (pintype "passive"))
      (node (ref "P6") (pin "4") (pinfunction "4_4") (pintype "passive"))
      (node (ref "P7") (pin "3") (pinfunction "GND_3") (pintype "passive"))
      (node (ref "P8") (pin "11") (pinfunction "GNDDetect_11") (pintype "passive"))
      (node (ref "P8") (pin "5") (pinfunction "GND_5") (pintype "passive"))
      (node (ref "P8") (pin "7") (pinfunction "GND_7") (pintype "passive"))
      (node (ref "P9") (pin "5") (pinfunction "GND_5") (pintype "passive"))
      (node (ref "R19") (pin "2") (pinfunction "2_2") (pintype "passive"))
      (node (ref "R84") (pin "1") (pinfunction "1_1") (pintype "passive"))
      (node (ref "R85") (pin "1") (pinfunction "1_1") (pintype "passive"))
      (node (ref "R94") (pin "2") (pinfunction "2_2") (pintype "passive"))
      (node (ref "SW6") (pin "1") (pinfunction "1_1") (pintype "passive"))
      (node (ref "SW6") (pin "3") (pinfunction "3_3") (pintype "passive"))
      (node (ref "SW8") (pin "1") (pinfunction "1_1") (pintype "passive"))
      (node (ref "SW9") (pin "1") (pinfunction "1_1") (pintype "passive"))
      (node (ref "U17") (pin "10") (pinfunction "VSS_10") (pintype "power_in"))
      (node (ref "U17") (pin "27") (pinfunction "VSS_27") (pintype "power_in"))
      (node (ref "U17") (pin "49") (pinfunction "VSS_49") (pintype "power_in"))
      (node (ref "U17") (pin "74") (pinfunction "VSS_74") (pintype "power_in"))
      (node (ref "U17") (pin "99") (pinfunction "VSS_99") (pintype "power_in"))
      (node (ref "U18") (pin "2") (pinfunction "GND_2") (pintype "passive"))
      (node (ref "U19") (pin "2") (pinfunction "GND_2") (pintype "power_in"))
      (node (ref "Y2") (pin "PAD") (pinfunction "PAD_PAD") (pintype "passive"))
    )
    (net (code "97") (name "Net-(D10-P$2)") (class "Default")
      (node (ref "C52") (pin "2") (pinfunction "2_2") (pintype "passive"))
      (node (ref "D10") (pin "2") (pinfunction "P$2_2") (pintype "passive"))
      (node (ref "R83") (pin "2") (pinfunction "2_2") (pintype "passive"))
      (node (ref "SW6") (pin "2") (pinfunction "2_2") (pintype "passive"))
      (node (ref "SW6") (pin "4") (pinfunction "4_4") (pintype "passive"))
    )
    (net (code "98") (name "Net-(D11-PadC)") (class "Default")
      (node (ref "D11") (pin "C") (pinfunction "C_C") (pintype "passive"))
      (node (ref "R19") (pin "1") (pinfunction "1_1") (pintype "passive"))
    )
    (net (code "99") (name "Net-(D13-PadC)") (class "Default")
      (node (ref "D13") (pin "C") (pinfunction "C_C") (pintype "passive"))
      (node (ref "R94") (pin "1") (pinfunction "1_1") (pintype "passive"))
    )
    (net (code "100") (name "Net-(P9-ID)") (class "Default")
      (node (ref "P9") (pin "4") (pinfunction "ID_4") (pintype "bidirectional"))
      (node (ref "TP25") (pin "1") (pinfunction "1_1") (pintype "passive"))
    )
    (net (code "101") (name "STAGND") (class "Default")
      (node (ref "C53") (pin "1") (pinfunction "1_1") (pintype "passive"))
      (node (ref "C54") (pin "1") (pinfunction "1_1") (pintype "passive"))
      (node (ref "C55") (pin "1") (pinfunction "1_1") (pintype "passive"))
      (node (ref "R84") (pin "2") (pinfunction "2_2") (pintype "passive"))
      (node (ref "U17") (pin "19") (pinfunction "VSSA_19") (pintype "power_in"))
      (node (ref "U17") (pin "20") (pinfunction "VREF-_20") (pintype "power_in"))
    )
    (net (code "102") (name "STAVCC") (class "Default")
      (node (ref "C53") (pin "2") (pinfunction "2_2") (pintype "passive"))
      (node (ref "C54") (pin "2") (pinfunction "2_2") (pintype "passive"))
      (node (ref "C55") (pin "2") (pinfunction "2_2") (pintype "passive"))
      (node (ref "R82") (pin "2") (pinfunction "2_2") (pintype "passive"))
      (node (ref "U17") (pin "21") (pinfunction "VREF+_21") (pintype "bidirectional"))
      (node (ref "U17") (pin "22") (pinfunction "VDDA_22") (pintype "power_in"))
    )
    (net (code "103") (name "unconnected-(P8-Reserved-Pad1)") (class "Default")
      (node (ref "P8") (pin "1") (pinfunction "Reserved_1") (pintype "passive+no_connect"))
    )
    (net (code "104") (name "unconnected-(P8-Reserved-Pad2)") (class "Default")
      (node (ref "P8") (pin "2") (pinfunction "Reserved_2") (pintype "passive+no_connect"))
    )
    (net (code "105") (name "unconnected-(U17A-PC4{slash}USART3_TX-Pad33)") (class "Default")
      (node (ref "U17") (pin "33") (pinfunction "PC4/USART3_TX_33") (pintype "bidirectional+no_connect"))
    )
  )
)
